# 5V-to-12V-Converter-ManyDiodes.net
KiCad netlist of a schematic drawn in EAGLE
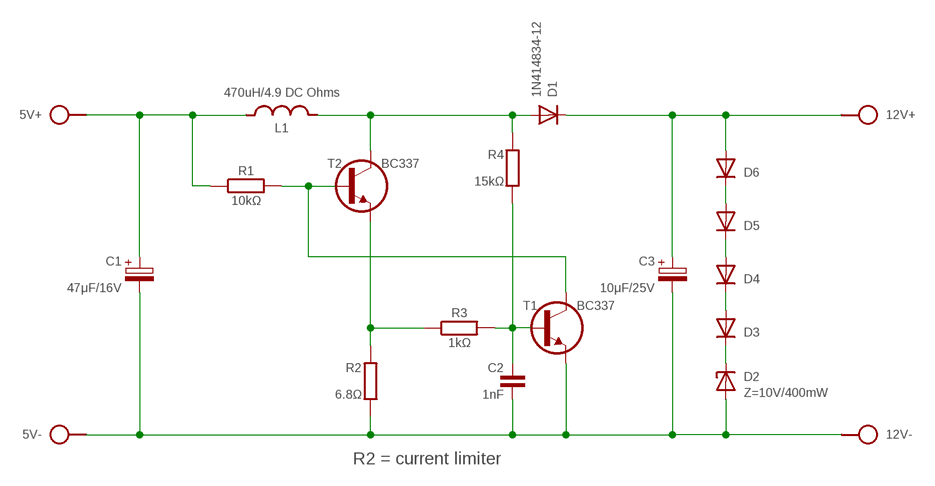
[diagram p0: schematic, sheet 1]

(export (version "E")
  (design (tool "Eeschema 10.0.6"))
  (components
    (comp (ref "5V")
      (value "SPAD+--+")
      (footprint "eagle-import:SPAD-+")
      (libsource (lib "eagle-import") (part "SPAD+--+"))
    )
    (comp (ref "12V")
      (value "SPAD+-+-")
      (footprint "eagle-import:SPAD+-")
      (libsource (lib "eagle-import") (part "SPAD+-+-"))
    )
    (comp (ref "C1")
      (value "47μF/16V")
      (footprint "eagle-import:E2.5-4_V")
      (libsource (lib "eagle-import") (part "CPOLE2,5-4/V"))
    )
    (comp (ref "C2")
      (value "1nF")
      (footprint "eagle-import:C050-020X036")
      (libsource (lib "eagle-import") (part "C050-020X036"))
    )
    (comp (ref "C3")
      (value "10μF/25V")
      (footprint "eagle-import:E2.5-4_V")
      (libsource (lib "eagle-import") (part "CPOLE2,5-4/V"))
    )
    (comp (ref "D1")
      (value "1N414834-12")
      (footprint "eagle-import:DO34-12")
      (libsource (lib "eagle-import") (part "1N414834-12"))
    )
    (comp (ref "D2")
      (value "Z=10V/400mW")
      (footprint "eagle-import:DO35Z10_V")
      (libsource (lib "eagle-import") (part "Z-DIODE-35Z10/V"))
    )
    (comp (ref "D3")
      (value "1N4002-2.54A")
      (footprint "eagle-import:DO35-2_54A")
      (libsource (lib "eagle-import") (part "1N4002-2.54A"))
    )
    (comp (ref "D4")
      (value "1N4002-2.54")
      (footprint "eagle-import:DO35-2_54")
      (libsource (lib "eagle-import") (part "1N4002-2.54"))
    )
    (comp (ref "D5")
      (value "1N4002-2.54A")
      (footprint "eagle-import:DO35-2_54A")
      (libsource (lib "eagle-import") (part "1N4002-2.54A"))
    )
    (comp (ref "D6")
      (value "1N4002-2.54")
      (footprint "eagle-import:DO35-2_54")
      (libsource (lib "eagle-import") (part "1N4002-2.54"))
    )
    (comp (ref "L1")
      (value "470uH/4.9 DC Ohms")
      (footprint "eagle-import:ED16-X")
      (libsource (lib "eagle-import") (part "L-SHORTED16-X"))
    )
    (comp (ref "R1")
      (value "10kΩ")
      (footprint "eagle-import:0204_7-V")
      (libsource (lib "eagle-import") (part "R-H0204/7-V"))
    )
    (comp (ref "R2")
      (value "6.8Ω")
      (footprint "eagle-import:0204_10")
      (libsource (lib "eagle-import") (part "R0204/10"))
    )
    (comp (ref "R3")
      (value "1kΩ")
      (footprint "eagle-import:0204_10")
      (libsource (lib "eagle-import") (part "R-H0204/10"))
    )
    (comp (ref "R4")
      (value "15kΩ")
      (footprint "eagle-import:0204_7-V")
      (libsource (lib "eagle-import") (part "R0204/7-V"))
    )
    (comp (ref "T1")
      (value "BC337")
      (footprint "eagle-import:TO92-CBE")
      (libsource (lib "eagle-import") (part "BC337CBE"))
    )
    (comp (ref "T2")
      (value "BC337")
      (footprint "eagle-import:TO92-CBE")
      (libsource (lib "eagle-import") (part "BC337CBE"))
    )
  )
  (nets
    (net (code "1") (name "Net-(5VA-P$1)") (class "Default")
      (node (ref "5V") (pin "2") (pinfunction "P$1_2") (pintype "passive"))
      (node (ref "C1") (pin "+") (pinfunction "+_+") (pintype "passive"))
      (node (ref "L1") (pin "1") (pinfunction "1_1") (pintype "passive"))
      (node (ref "R1") (pin "1") (pinfunction "1_1") (pintype "passive"))
    )
    (net (code "2") (name "Net-(12VA-P$1)") (class "Default")
      (node (ref "12V") (pin "2") (pinfunction "P$1_2") (pintype "passive"))
      (node (ref "C3") (pin "+") (pinfunction "+_+") (pintype "passive"))
      (node (ref "D1") (pin "C") (pinfunction "C_C") (pintype "passive"))
      (node (ref "D6") (pin "A") (pinfunction "A_A") (pintype "passive"))
    )
    (net (code "3") (name "Net-(12VB-P$1)") (class "Default")
      (node (ref "12V") (pin "1") (pinfunction "P$1_1") (pintype "passive"))
      (node (ref "5V") (pin "1") (pinfunction "P$1_1") (pintype "passive"))
      (node (ref "C1") (pin "-") (pinfunction "-_-") (pintype "passive"))
      (node (ref "C2") (pin "2") (pinfunction "2_2") (pintype "passive"))
      (node (ref "C3") (pin "-") (pinfunction "-_-") (pintype "passive"))
      (node (ref "D2") (pin "A") (pinfunction "A_A") (pintype "passive"))
      (node (ref "R2") (pin "1") (pinfunction "2_1") (pintype "passive"))
      (node (ref "T1") (pin "E") (pinfunction "E_E") (pintype "passive"))
    )
    (net (code "4") (name "Net-(D2-PadC)") (class "Default")
      (node (ref "D2") (pin "C") (pinfunction "C_C") (pintype "passive"))
      (node (ref "D3") (pin "C") (pinfunction "C_C") (pintype "passive"))
    )
    (net (code "5") (name "Net-(D3-PadA)") (class "Default")
      (node (ref "D3") (pin "A") (pinfunction "A_A") (pintype "passive"))
      (node (ref "D4") (pin "C") (pinfunction "C_C") (pintype "passive"))
    )
    (net (code "6") (name "Net-(D4-PadA)") (class "Default")
      (node (ref "D4") (pin "A") (pinfunction "A_A") (pintype "passive"))
      (node (ref "D5") (pin "C") (pinfunction "C_C") (pintype "passive"))
    )
    (net (code "7") (name "Net-(D5-PadA)") (class "Default")
      (node (ref "D5") (pin "A") (pinfunction "A_A") (pintype "passive"))
      (node (ref "D6") (pin "C") (pinfunction "C_C") (pintype "passive"))
    )
    (net (code "8") (name "Net-(R1-Pad2)") (class "Default")
      (node (ref "R1") (pin "2") (pinfunction "2_2") (pintype "passive"))
      (node (ref "T1") (pin "C") (pinfunction "C_C") (pintype "passive"))
      (node (ref "T2") (pin "B") (pinfunction "B_B") (pintype "passive"))
    )
    (net (code "9") (name "Net-(R2-1)") (class "Default")
      (node (ref "R2") (pin "2") (pinfunction "1_2") (pintype "passive"))
      (node (ref "R3") (pin "1") (pinfunction "1_1") (pintype "passive"))
      (node (ref "T2") (pin "E") (pinfunction "E_E") (pintype "passive"))
    )
    (net (code "10") (name "Net-(R4-1)") (class "Default")
      (node (ref "D1") (pin "A") (pinfunction "A_A") (pintype "passive"))
      (node (ref "L1") (pin "2") (pinfunction "2_2") (pintype "passive"))
      (node (ref "R4") (pin "2") (pinfunction "1_2") (pintype "passive"))
      (node (ref "T2") (pin "C") (pinfunction "C_C") (pintype "passive"))
    )
    (net (code "11") (name "Net-(R4-2)") (class "Default")
      (node (ref "C2") (pin "1") (pinfunction "1_1") (pintype "passive"))
      (node (ref "R3") (pin "2") (pinfunction "2_2") (pintype "passive"))
      (node (ref "R4") (pin "1") (pinfunction "2_1") (pintype "passive"))
      (node (ref "T1") (pin "B") (pinfunction "B_B") (pintype "passive"))
    )
  )
)
